# mymote-relay.net
KiCad netlist of a schematic drawn in EAGLE
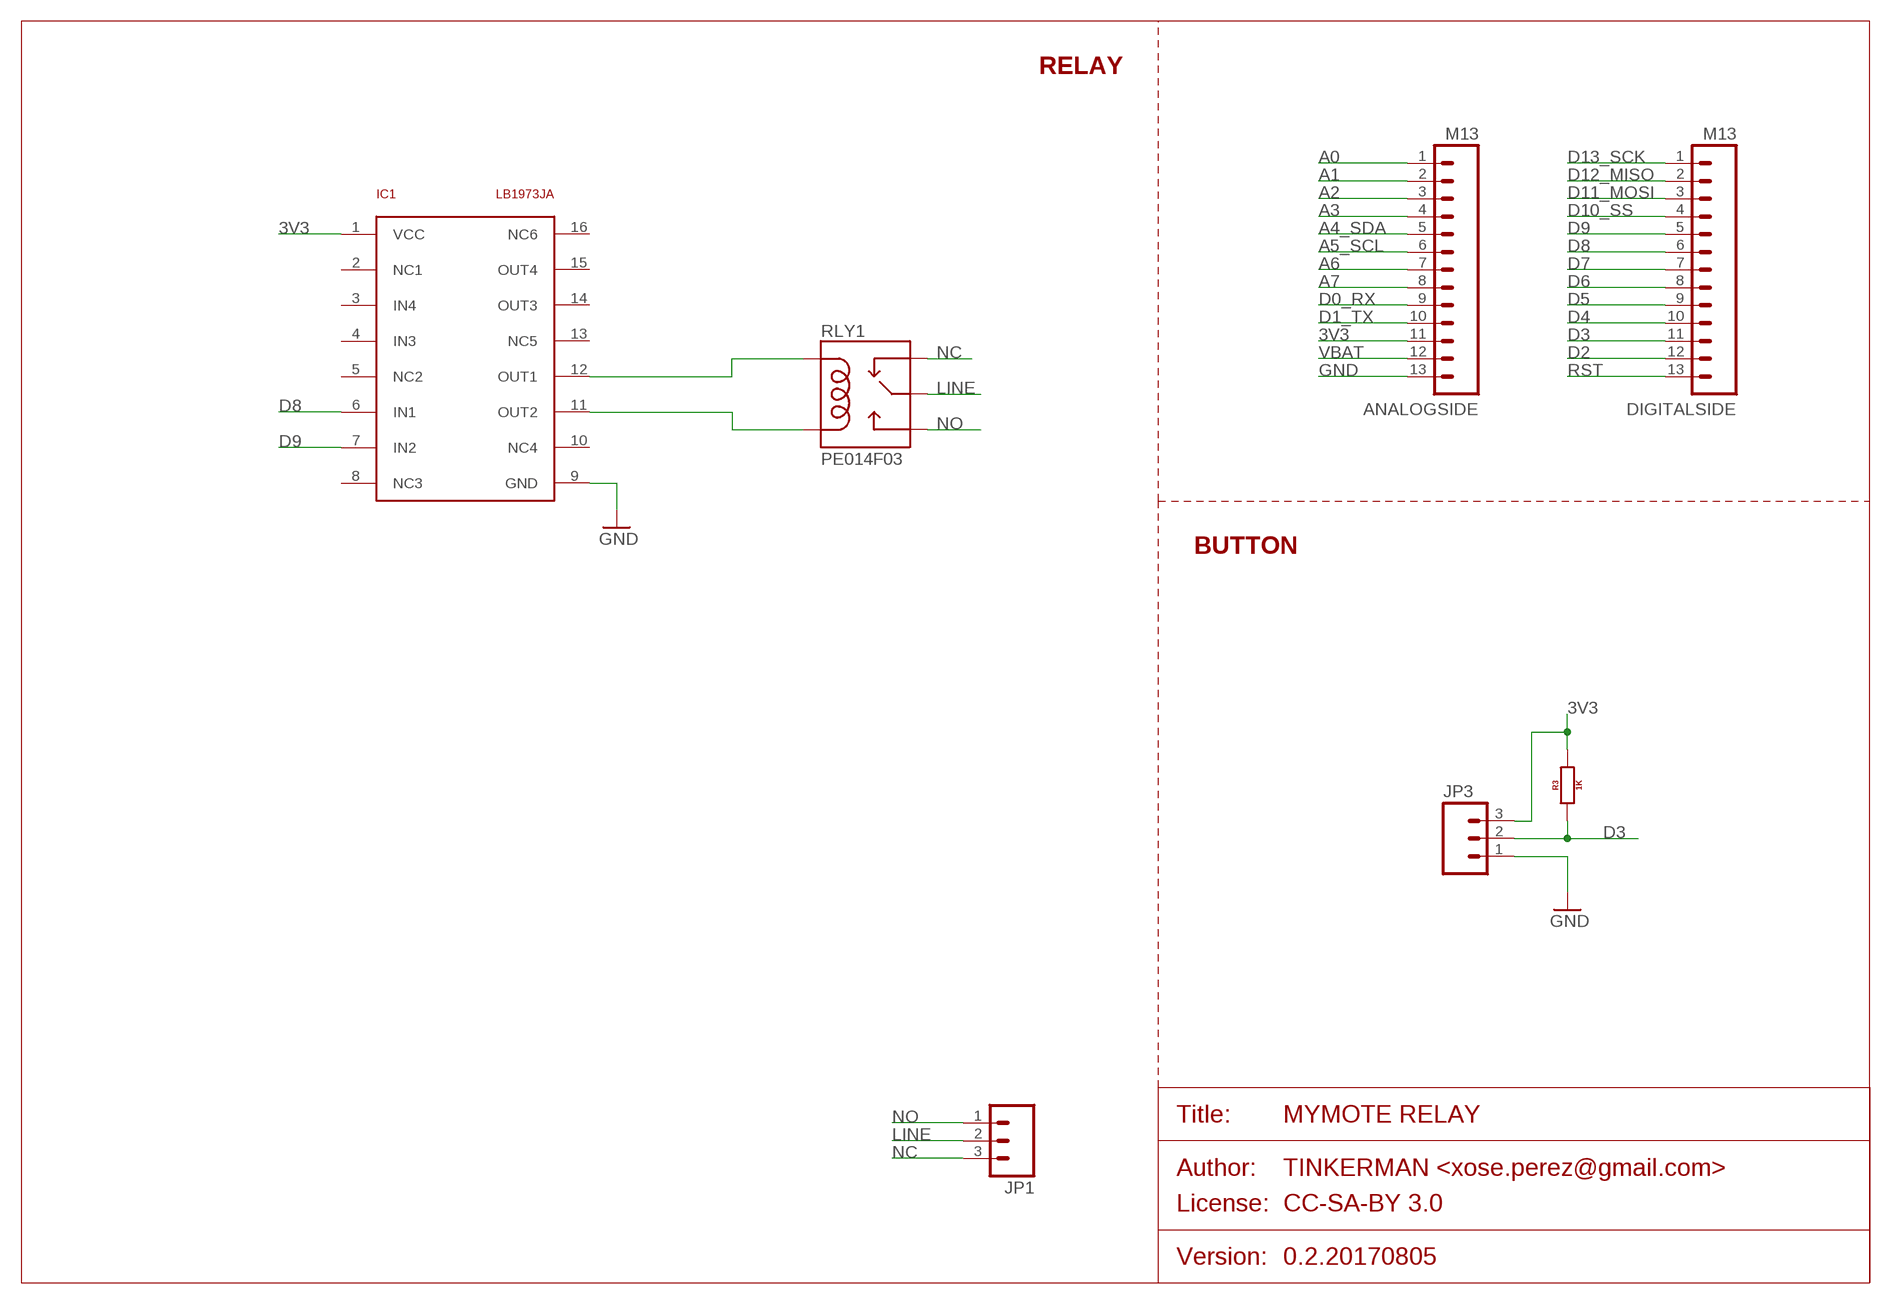
[diagram p0: schematic, sheet 1]

(export (version "E")
  (design (tool "Eeschema 10.0.6"))
  (components
    (comp (ref "ANALOGSIDE")
      (value "M13")
      (footprint "eagle-import:1X13_NO_SILK")
      (libsource (lib "eagle-import") (part "M13"))
    )
    (comp (ref "DIGITALSIDE")
      (value "M13")
      (footprint "eagle-import:1X13_NO_SILK")
      (libsource (lib "eagle-import") (part "M13"))
    )
    (comp (ref "IC1")
      (value "LB1973JA")
      (footprint "eagle-import:SSOP16")
      (libsource (lib "eagle-import") (part "LB1973JA"))
    )
    (comp (ref "JP1")
      (value "M03200MIL")
      (footprint "eagle-import:SCREWTERMINAL-200MIL-3")
      (libsource (lib "eagle-import") (part "M03200MIL"))
    )
    (comp (ref "JP3")
      (value "M03JST-PTH-VERT")
      (footprint "eagle-import:JST-3-PTH-VERT")
      (libsource (lib "eagle-import") (part "M03JST-PTH-VERT"))
    )
    (comp (ref "R3")
      (value "1K")
      (footprint "eagle-import:0805")
      (libsource (lib "eagle-import") (part "RESISTOR0805"))
    )
    (comp (ref "RLY1")
      (value "PE014F03")
      (footprint "eagle-import:PE014F0XX")
      (libsource (lib "eagle-import") (part "RELAYPE014FXX"))
    )
  )
  (nets
    (net (code "1") (name "/3V3") (class "Default")
      (node (ref "ANALOGSIDE") (pin "11") (pinfunction "11_11") (pintype "passive"))
      (node (ref "IC1") (pin "1") (pinfunction "VCC_1") (pintype "power_in"))
      (node (ref "JP3") (pin "3") (pinfunction "3_3") (pintype "passive"))
      (node (ref "R3") (pin "2") (pinfunction "2_2") (pintype "passive"))
    )
    (net (code "2") (name "/A0") (class "Default")
      (node (ref "ANALOGSIDE") (pin "1") (pinfunction "1_1") (pintype "passive"))
    )
    (net (code "3") (name "/A1") (class "Default")
      (node (ref "ANALOGSIDE") (pin "2") (pinfunction "2_2") (pintype "passive"))
    )
    (net (code "4") (name "/A2") (class "Default")
      (node (ref "ANALOGSIDE") (pin "3") (pinfunction "3_3") (pintype "passive"))
    )
    (net (code "5") (name "/A3") (class "Default")
      (node (ref "ANALOGSIDE") (pin "4") (pinfunction "4_4") (pintype "passive"))
    )
    (net (code "6") (name "/A4_SDA") (class "Default")
      (node (ref "ANALOGSIDE") (pin "5") (pinfunction "5_5") (pintype "passive"))
    )
    (net (code "7") (name "/A5_SCL") (class "Default")
      (node (ref "ANALOGSIDE") (pin "6") (pinfunction "6_6") (pintype "passive"))
    )
    (net (code "8") (name "/A6") (class "Default")
      (node (ref "ANALOGSIDE") (pin "7") (pinfunction "7_7") (pintype "passive"))
    )
    (net (code "9") (name "/A7") (class "Default")
      (node (ref "ANALOGSIDE") (pin "8") (pinfunction "8_8") (pintype "passive"))
    )
    (net (code "10") (name "/D0_RX") (class "Default")
      (node (ref "ANALOGSIDE") (pin "9") (pinfunction "9_9") (pintype "passive"))
    )
    (net (code "11") (name "/D1_TX") (class "Default")
      (node (ref "ANALOGSIDE") (pin "10") (pinfunction "10_10") (pintype "passive"))
    )
    (net (code "12") (name "/D2") (class "Default")
      (node (ref "DIGITALSIDE") (pin "12") (pinfunction "12_12") (pintype "passive"))
    )
    (net (code "13") (name "/D3") (class "Default")
      (node (ref "DIGITALSIDE") (pin "11") (pinfunction "11_11") (pintype "passive"))
      (node (ref "JP3") (pin "2") (pinfunction "2_2") (pintype "passive"))
      (node (ref "R3") (pin "1") (pinfunction "1_1") (pintype "passive"))
    )
    (net (code "14") (name "/D4") (class "Default")
      (node (ref "DIGITALSIDE") (pin "10") (pinfunction "10_10") (pintype "passive"))
    )
    (net (code "15") (name "/D5") (class "Default")
      (node (ref "DIGITALSIDE") (pin "9") (pinfunction "9_9") (pintype "passive"))
    )
    (net (code "16") (name "/D6") (class "Default")
      (node (ref "DIGITALSIDE") (pin "8") (pinfunction "8_8") (pintype "passive"))
    )
    (net (code "17") (name "/D7") (class "Default")
      (node (ref "DIGITALSIDE") (pin "7") (pinfunction "7_7") (pintype "passive"))
    )
    (net (code "18") (name "/D8") (class "Default")
      (node (ref "DIGITALSIDE") (pin "6") (pinfunction "6_6") (pintype "passive"))
      (node (ref "IC1") (pin "6") (pinfunction "IN1_6") (pintype "input"))
    )
    (net (code "19") (name "/D9") (class "Default")
      (node (ref "DIGITALSIDE") (pin "5") (pinfunction "5_5") (pintype "passive"))
      (node (ref "IC1") (pin "7") (pinfunction "IN2_7") (pintype "input"))
    )
    (net (code "20") (name "/D10_SS") (class "Default")
      (node (ref "DIGITALSIDE") (pin "4") (pinfunction "4_4") (pintype "passive"))
    )
    (net (code "21") (name "/D11_MOSI") (class "Default")
      (node (ref "DIGITALSIDE") (pin "3") (pinfunction "3_3") (pintype "passive"))
    )
    (net (code "22") (name "/D12_MISO") (class "Default")
      (node (ref "DIGITALSIDE") (pin "2") (pinfunction "2_2") (pintype "passive"))
    )
    (net (code "23") (name "/D13_SCK") (class "Default")
      (node (ref "DIGITALSIDE") (pin "1") (pinfunction "1_1") (pintype "passive"))
    )
    (net (code "24") (name "/LINE") (class "Default")
      (node (ref "JP1") (pin "2") (pinfunction "2_2") (pintype "passive"))
      (node (ref "RLY1") (pin "COMMON") (pinfunction "MAIN_COMMON") (pintype "bidirectional"))
    )
    (net (code "25") (name "/NC") (class "Default")
      (node (ref "JP1") (pin "3") (pinfunction "3_3") (pintype "passive"))
      (node (ref "RLY1") (pin "CLOSED") (pinfunction "NC_CLOSED") (pintype "bidirectional"))
    )
    (net (code "26") (name "/NO") (class "Default")
      (node (ref "JP1") (pin "1") (pinfunction "1_1") (pintype "passive"))
      (node (ref "RLY1") (pin "OPEN") (pinfunction "NO_OPEN") (pintype "bidirectional"))
    )
    (net (code "27") (name "/RST") (class "Default")
      (node (ref "DIGITALSIDE") (pin "13") (pinfunction "13_13") (pintype "passive"))
    )
    (net (code "28") (name "/VBAT") (class "Default")
      (node (ref "ANALOGSIDE") (pin "12") (pinfunction "12_12") (pintype "passive"))
    )
    (net (code "29") (name "GND") (class "Default")
      (node (ref "ANALOGSIDE") (pin "13") (pinfunction "13_13") (pintype "passive"))
      (node (ref "IC1") (pin "9") (pinfunction "GND_9") (pintype "power_in"))
      (node (ref "JP3") (pin "1") (pinfunction "1_1") (pintype "passive"))
    )
    (net (code "30") (name "Net-(IC1-OUT1)") (class "Default")
      (node (ref "IC1") (pin "12") (pinfunction "OUT1_12") (pintype "output"))
      (node (ref "RLY1") (pin "COIL1") (pinfunction "COIL1_COIL1") (pintype "bidirectional"))
    )
    (net (code "31") (name "Net-(IC1-OUT2)") (class "Default")
      (node (ref "IC1") (pin "11") (pinfunction "OUT2_11") (pintype "output"))
      (node (ref "RLY1") (pin "COIL2") (pinfunction "COIL2_COIL2") (pintype "bidirectional"))
    )
    (net (code "32") (name "unconnected-(IC1-IN3-Pad4)") (class "Default")
      (node (ref "IC1") (pin "4") (pinfunction "IN3_4") (pintype "input"))
    )
    (net (code "33") (name "unconnected-(IC1-IN4-Pad3)") (class "Default")
      (node (ref "IC1") (pin "3") (pinfunction "IN4_3") (pintype "input"))
    )
    (net (code "34") (name "unconnected-(IC1-NC1-Pad2)") (class "Default")
      (node (ref "IC1") (pin "2") (pinfunction "NC1_2") (pintype "no_connect"))
    )
    (net (code "35") (name "unconnected-(IC1-NC2-Pad5)") (class "Default")
      (node (ref "IC1") (pin "5") (pinfunction "NC2_5") (pintype "no_connect"))
    )
    (net (code "36") (name "unconnected-(IC1-NC3-Pad8)") (class "Default")
      (node (ref "IC1") (pin "8") (pinfunction "NC3_8") (pintype "no_connect"))
    )
    (net (code "37") (name "unconnected-(IC1-NC4-Pad10)") (class "Default")
      (node (ref "IC1") (pin "10") (pinfunction "NC4_10") (pintype "no_connect"))
    )
    (net (code "38") (name "unconnected-(IC1-NC5-Pad13)") (class "Default")
      (node (ref "IC1") (pin "13") (pinfunction "NC5_13") (pintype "no_connect"))
    )
    (net (code "39") (name "unconnected-(IC1-NC6-Pad16)") (class "Default")
      (node (ref "IC1") (pin "16") (pinfunction "NC6_16") (pintype "no_connect"))
    )
    (net (code "40") (name "unconnected-(IC1-OUT3-Pad14)") (class "Default")
      (node (ref "IC1") (pin "14") (pinfunction "OUT3_14") (pintype "output"))
    )
    (net (code "41") (name "unconnected-(IC1-OUT4-Pad15)") (class "Default")
      (node (ref "IC1") (pin "15") (pinfunction "OUT4_15") (pintype "output"))
    )
  )
)
